# MainBoard_V0_5.net
KiCad netlist of a schematic drawn in EAGLE
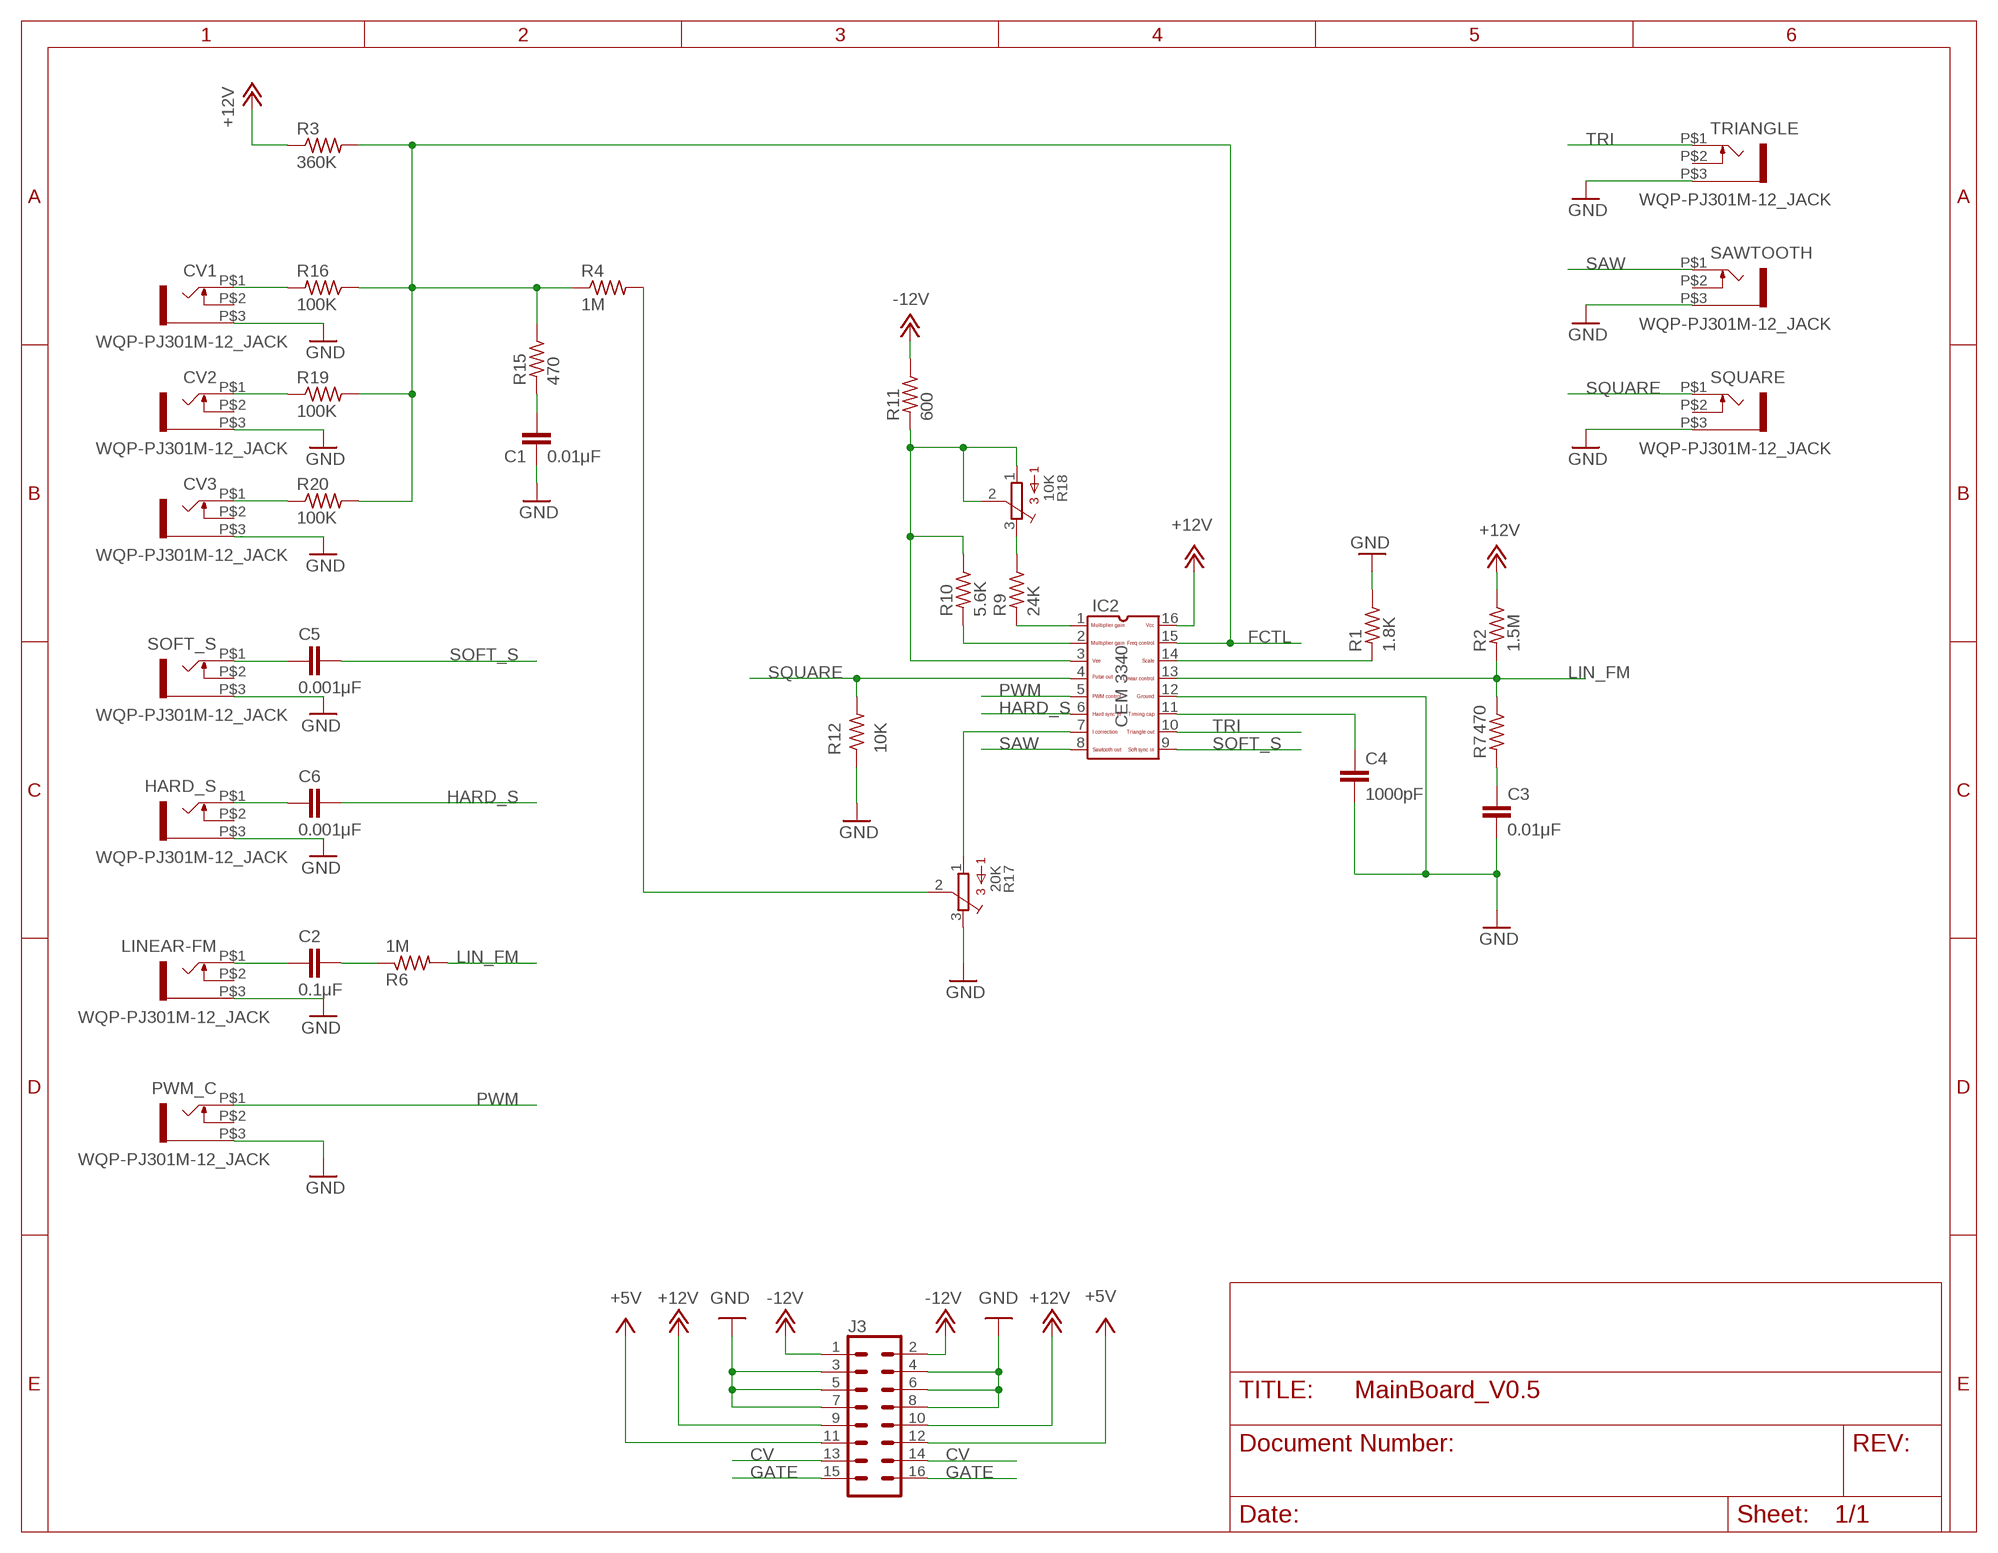
[diagram p0: schematic, sheet 1]

(export (version "E")
  (design (tool "Eeschema 10.0.6"))
  (components
    (comp (ref "C1")
      (value "0.01μF")
      (footprint "eagle-import:C050-025X075")
      (libsource (lib "eagle-import") (part "C-EU050-025X075"))
    )
    (comp (ref "C2")
      (value "0.1μF")
      (footprint "eagle-import:C050-025X075")
      (libsource (lib "eagle-import") (part "C-EU050-025X075"))
    )
    (comp (ref "C3")
      (value "0.01μF")
      (footprint "eagle-import:C050-025X075")
      (libsource (lib "eagle-import") (part "C-EU050-025X075"))
    )
    (comp (ref "C4")
      (value "1000pF")
      (footprint "eagle-import:C050-025X075")
      (libsource (lib "eagle-import") (part "C-EU050-025X075"))
    )
    (comp (ref "C5")
      (value "0.001μF")
      (footprint "eagle-import:C050-025X075")
      (libsource (lib "eagle-import") (part "C-EU050-025X075"))
    )
    (comp (ref "C6")
      (value "0.001μF")
      (footprint "eagle-import:C050-025X075")
      (libsource (lib "eagle-import") (part "C-EU050-025X075"))
    )
    (comp (ref "CV1")
      (value "WQP-PJ301M-12_JACK")
      (footprint "eagle-import:WQP-PJ301M-12_JACK")
      (libsource (lib "eagle-import") (part "WQP-PJ301M-12_JACK"))
    )
    (comp (ref "CV2")
      (value "WQP-PJ301M-12_JACK")
      (footprint "eagle-import:WQP-PJ301M-12_JACK")
      (fields (field (name "SPICEPREFIX") "U"))
      (libsource (lib "eagle-import") (part "WQP-PJ301M-12_JACK"))
    )
    (comp (ref "CV3")
      (value "WQP-PJ301M-12_JACK")
      (footprint "eagle-import:WQP-PJ301M-12_JACK")
      (libsource (lib "eagle-import") (part "WQP-PJ301M-12_JACK"))
    )
    (comp (ref "HARD_S")
      (value "WQP-PJ301M-12_JACK")
      (footprint "eagle-import:WQP-PJ301M-12_JACK")
      (libsource (lib "eagle-import") (part "WQP-PJ301M-12_JACK"))
    )
    (comp (ref "IC2")
      (value "CEM3340")
      (footprint "eagle-import:DIL16")
      (libsource (lib "eagle-import") (part "CEM3340"))
    )
    (comp (ref "J3")
      (value "CONN_08X2_SHROUD")
      (footprint "eagle-import:2X8-SHROUDED_LOCK")
      (libsource (lib "eagle-import") (part "CONN_08X2_SHROUD"))
    )
    (comp (ref "LINEAR-FM")
      (value "WQP-PJ301M-12_JACK")
      (footprint "eagle-import:WQP-PJ301M-12_JACK")
      (libsource (lib "eagle-import") (part "WQP-PJ301M-12_JACK"))
    )
    (comp (ref "PWM_C")
      (value "WQP-PJ301M-12_JACK")
      (footprint "eagle-import:WQP-PJ301M-12_JACK")
      (libsource (lib "eagle-import") (part "WQP-PJ301M-12_JACK"))
    )
    (comp (ref "R1")
      (value "1.8K")
      (footprint "eagle-import:0207_10")
      (libsource (lib "eagle-import") (part "R-US_0207/10"))
    )
    (comp (ref "R2")
      (value "1.5M")
      (footprint "eagle-import:0207_10")
      (libsource (lib "eagle-import") (part "R-US_0207/10"))
    )
    (comp (ref "R3")
      (value "360K")
      (footprint "eagle-import:0207_10")
      (libsource (lib "eagle-import") (part "R-US_0207/10"))
    )
    (comp (ref "R4")
      (value "1M")
      (footprint "eagle-import:0207_10")
      (libsource (lib "eagle-import") (part "R-US_0207/10"))
    )
    (comp (ref "R6")
      (value "1M")
      (footprint "eagle-import:0207_10")
      (libsource (lib "eagle-import") (part "R-US_0207/10"))
    )
    (comp (ref "R7")
      (value "470")
      (footprint "eagle-import:0207_10")
      (libsource (lib "eagle-import") (part "R-US_0207/10"))
    )
    (comp (ref "R9")
      (value "24K")
      (footprint "eagle-import:0207_10")
      (libsource (lib "eagle-import") (part "R-US_0207/10"))
    )
    (comp (ref "R10")
      (value "5.6K")
      (footprint "eagle-import:0207_10")
      (libsource (lib "eagle-import") (part "R-US_0207/10"))
    )
    (comp (ref "R11")
      (value "600")
      (footprint "eagle-import:0207_10")
      (libsource (lib "eagle-import") (part "R-US_0207/10"))
    )
    (comp (ref "R12")
      (value "10K")
      (footprint "eagle-import:0207_10")
      (libsource (lib "eagle-import") (part "R-US_0207/10"))
    )
    (comp (ref "R15")
      (value "470")
      (footprint "eagle-import:0207_10")
      (libsource (lib "eagle-import") (part "R-US_0207/10"))
    )
    (comp (ref "R16")
      (value "100K")
      (footprint "eagle-import:0207_10")
      (libsource (lib "eagle-import") (part "R-US_0207/10"))
    )
    (comp (ref "R17")
      (value "20K")
      (footprint "eagle-import:3386W")
      (libsource (lib "eagle-import") (part "3386-W"))
    )
    (comp (ref "R18")
      (value "10K")
      (footprint "eagle-import:3386W")
      (libsource (lib "eagle-import") (part "3386-W"))
    )
    (comp (ref "R19")
      (value "100K")
      (footprint "eagle-import:0207_10")
      (libsource (lib "eagle-import") (part "R-US_0207/10"))
    )
    (comp (ref "R20")
      (value "100K")
      (footprint "eagle-import:0207_10")
      (libsource (lib "eagle-import") (part "R-US_0207/10"))
    )
    (comp (ref "SAWTOOTH")
      (value "WQP-PJ301M-12_JACK")
      (footprint "eagle-import:WQP-PJ301M-12_JACK")
      (libsource (lib "eagle-import") (part "WQP-PJ301M-12_JACK"))
    )
    (comp (ref "SOFT_S")
      (value "WQP-PJ301M-12_JACK")
      (footprint "eagle-import:WQP-PJ301M-12_JACK")
      (libsource (lib "eagle-import") (part "WQP-PJ301M-12_JACK"))
    )
    (comp (ref "SQUARE")
      (value "WQP-PJ301M-12_JACK")
      (footprint "eagle-import:WQP-PJ301M-12_JACK")
      (libsource (lib "eagle-import") (part "WQP-PJ301M-12_JACK"))
    )
    (comp (ref "TRIANGLE")
      (value "WQP-PJ301M-12_JACK")
      (footprint "eagle-import:WQP-PJ301M-12_JACK")
      (libsource (lib "eagle-import") (part "WQP-PJ301M-12_JACK"))
    )
  )
  (nets
    (net (code "1") (name "+5V") (class "Default")
      (node (ref "J3") (pin "11") (pinfunction "11_11") (pintype "passive"))
      (node (ref "J3") (pin "12") (pinfunction "12_12") (pintype "passive"))
    )
    (net (code "2") (name "+12V") (class "Default")
      (node (ref "IC2") (pin "16") (pinfunction "16_16") (pintype "power_in"))
      (node (ref "J3") (pin "10") (pinfunction "10_10") (pintype "passive"))
      (node (ref "J3") (pin "9") (pinfunction "9_9") (pintype "passive"))
      (node (ref "R2") (pin "1") (pinfunction "1_1") (pintype "passive"))
      (node (ref "R3") (pin "1") (pinfunction "1_1") (pintype "passive"))
    )
    (net (code "3") (name "-12V") (class "Default")
      (node (ref "J3") (pin "1") (pinfunction "1_1") (pintype "passive"))
      (node (ref "J3") (pin "2") (pinfunction "2_2") (pintype "passive"))
      (node (ref "R11") (pin "1") (pinfunction "1_1") (pintype "passive"))
    )
    (net (code "4") (name "/CV") (class "Default")
      (node (ref "J3") (pin "13") (pinfunction "13_13") (pintype "passive"))
      (node (ref "J3") (pin "14") (pinfunction "14_14") (pintype "passive"))
    )
    (net (code "5") (name "/FCTL") (class "Default")
      (node (ref "IC2") (pin "15") (pinfunction "15_15") (pintype "input"))
      (node (ref "R15") (pin "1") (pinfunction "1_1") (pintype "passive"))
      (node (ref "R16") (pin "1") (pinfunction "1_1") (pintype "passive"))
      (node (ref "R19") (pin "2") (pinfunction "2_2") (pintype "passive"))
      (node (ref "R20") (pin "2") (pinfunction "2_2") (pintype "passive"))
      (node (ref "R3") (pin "2") (pinfunction "2_2") (pintype "passive"))
      (node (ref "R4") (pin "1") (pinfunction "1_1") (pintype "passive"))
    )
    (net (code "6") (name "/GATE") (class "Default")
      (node (ref "J3") (pin "15") (pinfunction "15_15") (pintype "passive"))
      (node (ref "J3") (pin "16") (pinfunction "16_16") (pintype "passive"))
    )
    (net (code "7") (name "/HARD_S") (class "Default")
      (node (ref "C6") (pin "2") (pinfunction "2_2") (pintype "passive"))
      (node (ref "IC2") (pin "6") (pinfunction "6_6") (pintype "input"))
    )
    (net (code "8") (name "/LIN_FM") (class "Default")
      (node (ref "IC2") (pin "13") (pinfunction "13_13") (pintype "input"))
      (node (ref "R2") (pin "2") (pinfunction "2_2") (pintype "passive"))
      (node (ref "R6") (pin "2") (pinfunction "2_2") (pintype "passive"))
      (node (ref "R7") (pin "1") (pinfunction "1_1") (pintype "passive"))
    )
    (net (code "9") (name "/PWM") (class "Default")
      (node (ref "IC2") (pin "5") (pinfunction "5_5") (pintype "input"))
      (node (ref "PWM_C") (pin "P$1") (pinfunction "2_P$1") (pintype "passive"))
    )
    (net (code "10") (name "/SAW") (class "Default")
      (node (ref "IC2") (pin "8") (pinfunction "8_8") (pintype "output"))
      (node (ref "SAWTOOTH") (pin "P$1") (pinfunction "2_P$1") (pintype "passive"))
    )
    (net (code "11") (name "/SOFT_S") (class "Default")
      (node (ref "C5") (pin "1") (pinfunction "1_1") (pintype "passive"))
      (node (ref "IC2") (pin "9") (pinfunction "9_9") (pintype "input"))
    )
    (net (code "12") (name "/SQUARE") (class "Default")
      (node (ref "IC2") (pin "4") (pinfunction "4_4") (pintype "output"))
      (node (ref "R12") (pin "2") (pinfunction "2_2") (pintype "passive"))
      (node (ref "SQUARE") (pin "P$1") (pinfunction "2_P$1") (pintype "passive"))
    )
    (net (code "13") (name "/TRI") (class "Default")
      (node (ref "IC2") (pin "10") (pinfunction "10_10") (pintype "output"))
      (node (ref "TRIANGLE") (pin "P$1") (pinfunction "2_P$1") (pintype "passive"))
    )
    (net (code "14") (name "GND") (class "Default")
      (node (ref "C1") (pin "2") (pinfunction "2_2") (pintype "passive"))
      (node (ref "C3") (pin "2") (pinfunction "2_2") (pintype "passive"))
      (node (ref "C4") (pin "2") (pinfunction "2_2") (pintype "passive"))
      (node (ref "CV1") (pin "P$3") (pinfunction "1_P$3") (pintype "passive"))
      (node (ref "CV2") (pin "P$3") (pinfunction "1_P$3") (pintype "passive"))
      (node (ref "CV3") (pin "P$3") (pinfunction "1_P$3") (pintype "passive"))
      (node (ref "HARD_S") (pin "P$3") (pinfunction "1_P$3") (pintype "passive"))
      (node (ref "IC2") (pin "12") (pinfunction "12_12") (pintype "power_in"))
      (node (ref "J3") (pin "3") (pinfunction "3_3") (pintype "passive"))
      (node (ref "J3") (pin "4") (pinfunction "4_4") (pintype "passive"))
      (node (ref "J3") (pin "5") (pinfunction "5_5") (pintype "passive"))
      (node (ref "J3") (pin "6") (pinfunction "6_6") (pintype "passive"))
      (node (ref "J3") (pin "7") (pinfunction "7_7") (pintype "passive"))
      (node (ref "J3") (pin "8") (pinfunction "8_8") (pintype "passive"))
      (node (ref "LINEAR-FM") (pin "P$3") (pinfunction "1_P$3") (pintype "passive"))
      (node (ref "PWM_C") (pin "P$3") (pinfunction "1_P$3") (pintype "passive"))
      (node (ref "R1") (pin "1") (pinfunction "1_1") (pintype "passive"))
      (node (ref "R12") (pin "1") (pinfunction "1_1") (pintype "passive"))
      (node (ref "R17") (pin "3") (pinfunction "3_3") (pintype "passive"))
      (node (ref "SAWTOOTH") (pin "P$3") (pinfunction "1_P$3") (pintype "passive"))
      (node (ref "SOFT_S") (pin "P$3") (pinfunction "1_P$3") (pintype "passive"))
      (node (ref "SQUARE") (pin "P$3") (pinfunction "1_P$3") (pintype "passive"))
      (node (ref "TRIANGLE") (pin "P$3") (pinfunction "1_P$3") (pintype "passive"))
    )
    (net (code "15") (name "Net-(C1-Pad1)") (class "Default")
      (node (ref "C1") (pin "1") (pinfunction "1_1") (pintype "passive"))
      (node (ref "R15") (pin "2") (pinfunction "2_2") (pintype "passive"))
    )
    (net (code "16") (name "Net-(C2-Pad2)") (class "Default")
      (node (ref "C2") (pin "2") (pinfunction "2_2") (pintype "passive"))
      (node (ref "R6") (pin "1") (pinfunction "1_1") (pintype "passive"))
    )
    (net (code "17") (name "Net-(C3-Pad1)") (class "Default")
      (node (ref "C3") (pin "1") (pinfunction "1_1") (pintype "passive"))
      (node (ref "R7") (pin "2") (pinfunction "2_2") (pintype "passive"))
    )
    (net (code "18") (name "Net-(C4-Pad1)") (class "Default")
      (node (ref "C4") (pin "1") (pinfunction "1_1") (pintype "passive"))
      (node (ref "IC2") (pin "11") (pinfunction "11_11") (pintype "bidirectional"))
    )
    (net (code "19") (name "Net-(CV1-2)") (class "Default")
      (node (ref "CV1") (pin "P$1") (pinfunction "2_P$1") (pintype "passive"))
      (node (ref "R16") (pin "2") (pinfunction "2_2") (pintype "passive"))
    )
    (net (code "20") (name "Net-(CV2-2)") (class "Default")
      (node (ref "CV2") (pin "P$1") (pinfunction "2_P$1") (pintype "passive"))
      (node (ref "R19") (pin "1") (pinfunction "1_1") (pintype "passive"))
    )
    (net (code "21") (name "Net-(CV3-2)") (class "Default")
      (node (ref "CV3") (pin "P$1") (pinfunction "2_P$1") (pintype "passive"))
      (node (ref "R20") (pin "1") (pinfunction "1_1") (pintype "passive"))
    )
    (net (code "22") (name "Net-(HARD_S-2)") (class "Default")
      (node (ref "C6") (pin "1") (pinfunction "1_1") (pintype "passive"))
      (node (ref "HARD_S") (pin "P$1") (pinfunction "2_P$1") (pintype "passive"))
    )
    (net (code "23") (name "Net-(IC2-Pad1)") (class "Default")
      (node (ref "IC2") (pin "1") (pinfunction "1_1") (pintype "bidirectional"))
      (node (ref "R9") (pin "2") (pinfunction "2_2") (pintype "passive"))
    )
    (net (code "24") (name "Net-(IC2-Pad2)") (class "Default")
      (node (ref "IC2") (pin "2") (pinfunction "2_2") (pintype "bidirectional"))
      (node (ref "R10") (pin "2") (pinfunction "2_2") (pintype "passive"))
    )
    (net (code "25") (name "Net-(IC2-Pad3)") (class "Default")
      (node (ref "IC2") (pin "3") (pinfunction "3_3") (pintype "power_in"))
      (node (ref "R10") (pin "1") (pinfunction "1_1") (pintype "passive"))
      (node (ref "R11") (pin "2") (pinfunction "2_2") (pintype "passive"))
      (node (ref "R18") (pin "1") (pinfunction "1_1") (pintype "passive"))
      (node (ref "R18") (pin "2") (pinfunction "2_2") (pintype "passive"))
    )
    (net (code "26") (name "Net-(IC2-Pad7)") (class "Default")
      (node (ref "IC2") (pin "7") (pinfunction "7_7") (pintype "bidirectional"))
      (node (ref "R17") (pin "1") (pinfunction "1_1") (pintype "passive"))
    )
    (net (code "27") (name "Net-(IC2-Pad14)") (class "Default")
      (node (ref "IC2") (pin "14") (pinfunction "14_14") (pintype "input"))
      (node (ref "R1") (pin "2") (pinfunction "2_2") (pintype "passive"))
    )
    (net (code "28") (name "Net-(LINEAR-FM-2)") (class "Default")
      (node (ref "C2") (pin "1") (pinfunction "1_1") (pintype "passive"))
      (node (ref "LINEAR-FM") (pin "P$1") (pinfunction "2_P$1") (pintype "passive"))
    )
    (net (code "29") (name "Net-(R17-Pad2)") (class "Default")
      (node (ref "R17") (pin "2") (pinfunction "2_2") (pintype "passive"))
      (node (ref "R4") (pin "2") (pinfunction "2_2") (pintype "passive"))
    )
    (net (code "30") (name "Net-(R18-Pad3)") (class "Default")
      (node (ref "R18") (pin "3") (pinfunction "3_3") (pintype "passive"))
      (node (ref "R9") (pin "1") (pinfunction "1_1") (pintype "passive"))
    )
    (net (code "31") (name "Net-(SOFT_S-2)") (class "Default")
      (node (ref "C5") (pin "2") (pinfunction "2_2") (pintype "passive"))
      (node (ref "SOFT_S") (pin "P$1") (pinfunction "2_P$1") (pintype "passive"))
    )
    (net (code "32") (name "unconnected-(CV1-3-PadP$2)") (class "Default")
      (node (ref "CV1") (pin "P$2") (pinfunction "3_P$2") (pintype "passive"))
    )
    (net (code "33") (name "unconnected-(CV2-3-PadP$2)") (class "Default")
      (node (ref "CV2") (pin "P$2") (pinfunction "3_P$2") (pintype "passive"))
    )
    (net (code "34") (name "unconnected-(CV3-3-PadP$2)") (class "Default")
      (node (ref "CV3") (pin "P$2") (pinfunction "3_P$2") (pintype "passive"))
    )
    (net (code "35") (name "unconnected-(HARD_S-3-PadP$2)") (class "Default")
      (node (ref "HARD_S") (pin "P$2") (pinfunction "3_P$2") (pintype "passive"))
    )
    (net (code "36") (name "unconnected-(LINEAR-FM-3-PadP$2)") (class "Default")
      (node (ref "LINEAR-FM") (pin "P$2") (pinfunction "3_P$2") (pintype "passive"))
    )
    (net (code "37") (name "unconnected-(PWM_C-3-PadP$2)") (class "Default")
      (node (ref "PWM_C") (pin "P$2") (pinfunction "3_P$2") (pintype "passive"))
    )
    (net (code "38") (name "unconnected-(SAWTOOTH-3-PadP$2)") (class "Default")
      (node (ref "SAWTOOTH") (pin "P$2") (pinfunction "3_P$2") (pintype "passive"))
    )
    (net (code "39") (name "unconnected-(SOFT_S-3-PadP$2)") (class "Default")
      (node (ref "SOFT_S") (pin "P$2") (pinfunction "3_P$2") (pintype "passive"))
    )
    (net (code "40") (name "unconnected-(SQUARE-3-PadP$2)") (class "Default")
      (node (ref "SQUARE") (pin "P$2") (pinfunction "3_P$2") (pintype "passive"))
    )
    (net (code "41") (name "unconnected-(TRIANGLE-3-PadP$2)") (class "Default")
      (node (ref "TRIANGLE") (pin "P$2") (pinfunction "3_P$2") (pintype "passive"))
    )
  )
)
